# display.net
KiCad netlist of a schematic drawn in EAGLE
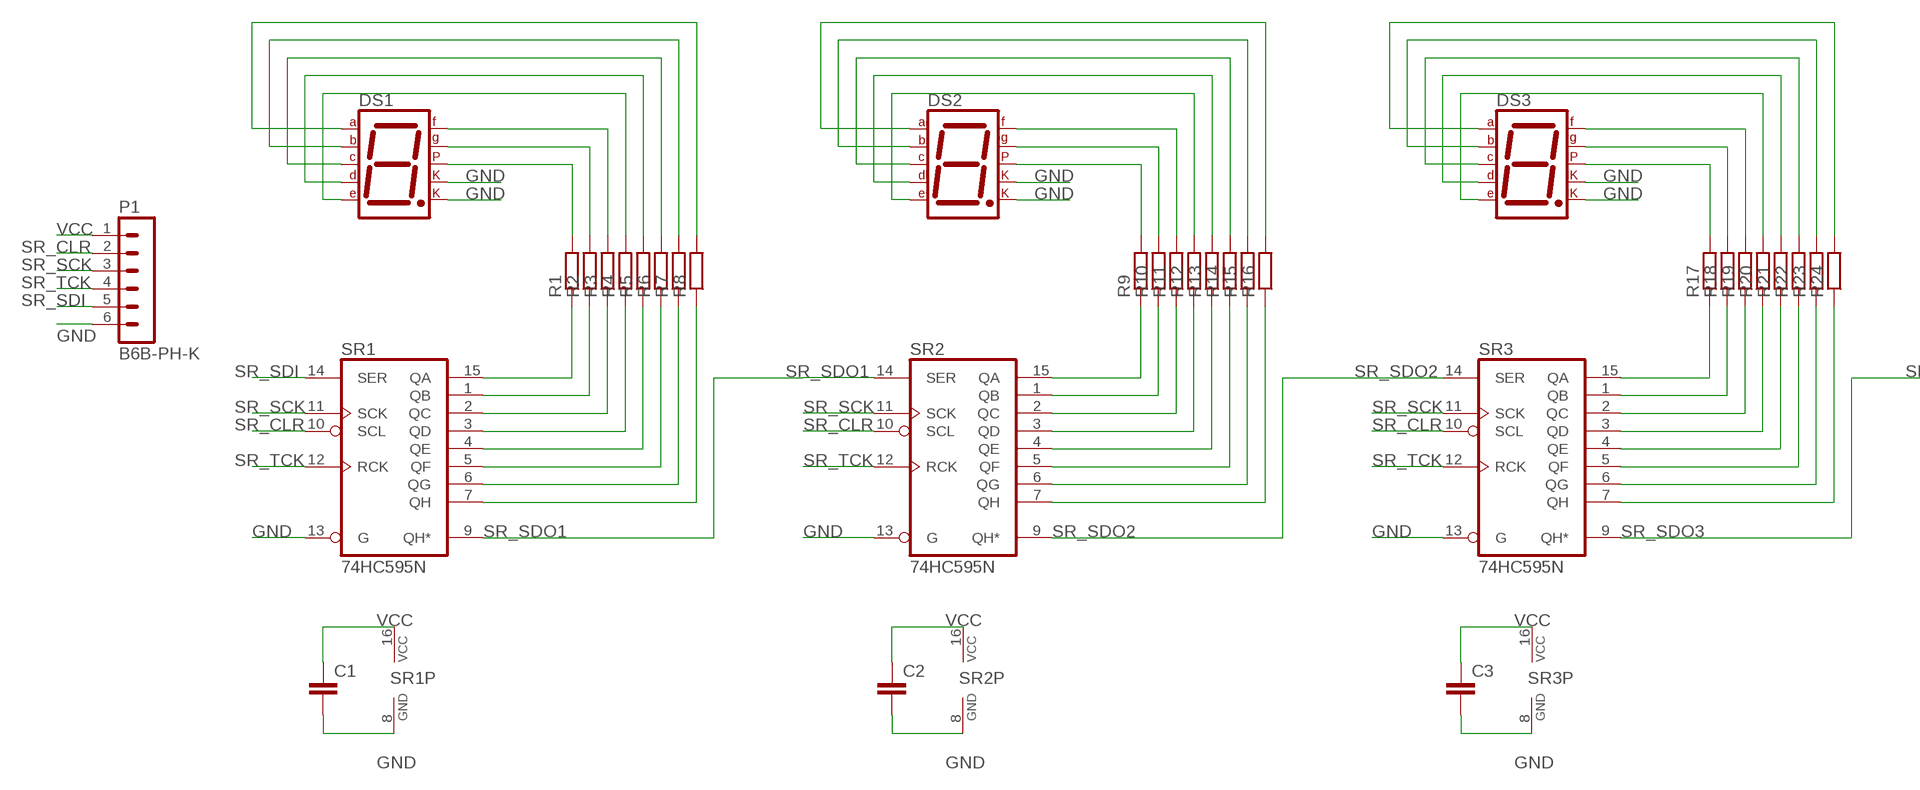
[diagram p0: schematic, sheet 1, part 1 of 2]
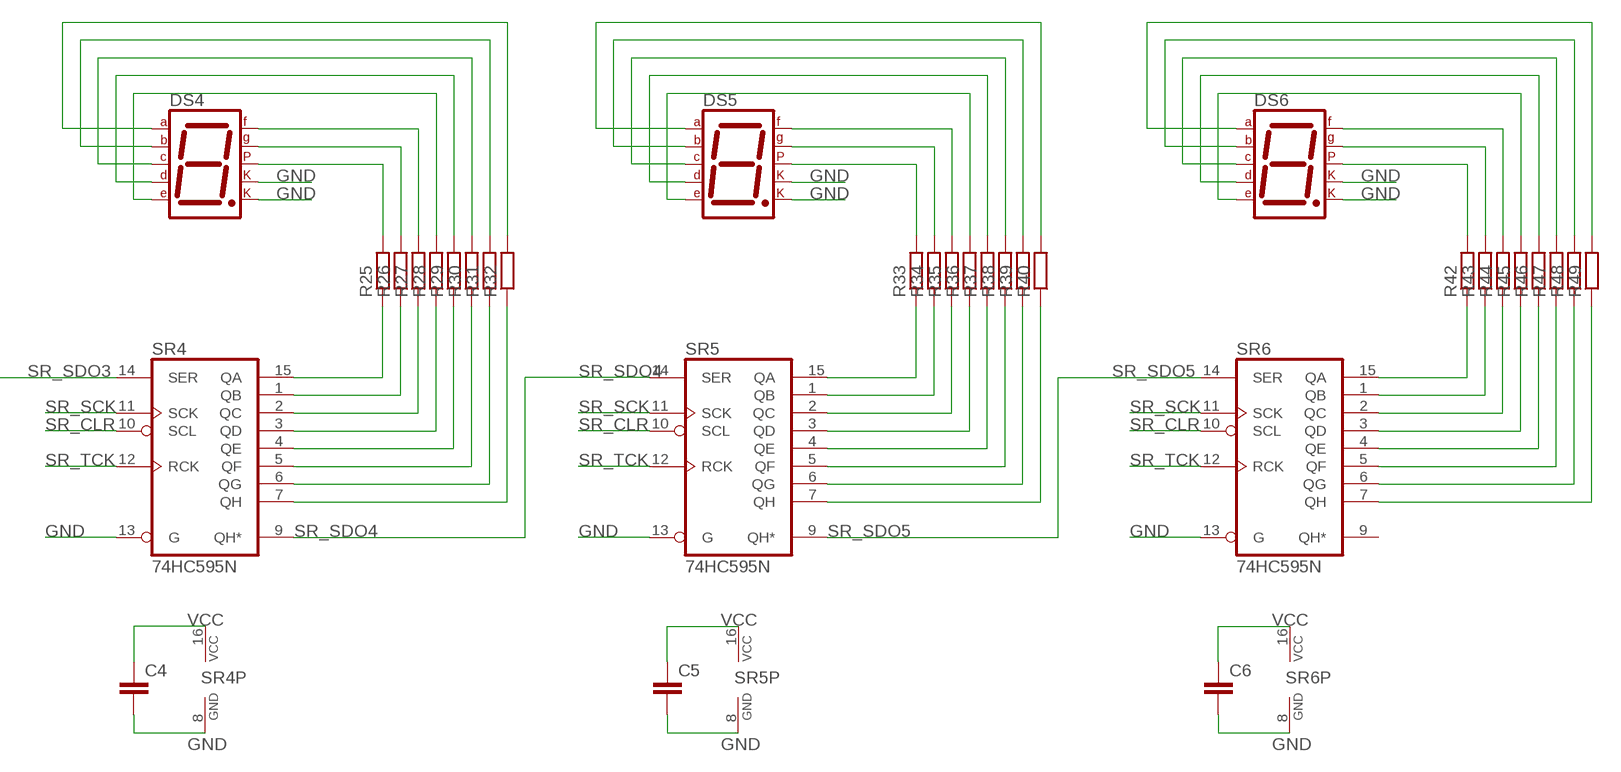
[diagram p1: schematic, sheet 1, part 2 of 2]

(export (version "E")
  (design (tool "Eeschema 10.0.6"))
  (components
    (comp (ref "C1")
      (value "C-EU025-024X044")
      (footprint "eagle-import:C025-024X044")
      (libsource (lib "eagle-import") (part "C-EU025-024X044"))
    )
    (comp (ref "C2")
      (value "C-EU025-024X044")
      (footprint "eagle-import:C025-024X044")
      (libsource (lib "eagle-import") (part "C-EU025-024X044"))
    )
    (comp (ref "C3")
      (value "C-EU025-024X044")
      (footprint "eagle-import:C025-024X044")
      (libsource (lib "eagle-import") (part "C-EU025-024X044"))
    )
    (comp (ref "C4")
      (value "C-EU025-024X044")
      (footprint "eagle-import:C025-024X044")
      (libsource (lib "eagle-import") (part "C-EU025-024X044"))
    )
    (comp (ref "C5")
      (value "C-EU025-024X044")
      (footprint "eagle-import:C025-024X044")
      (libsource (lib "eagle-import") (part "C-EU025-024X044"))
    )
    (comp (ref "C6")
      (value "C-EU025-024X044")
      (footprint "eagle-import:C025-024X044")
      (libsource (lib "eagle-import") (part "C-EU025-024X044"))
    )
    (comp (ref "DS1")
      (value "7SEG-CK")
      (footprint "eagle-import:7SEG-13")
      (libsource (lib "eagle-import") (part "7SEG-CK"))
    )
    (comp (ref "DS2")
      (value "7SEG-CK")
      (footprint "eagle-import:7SEG-13")
      (libsource (lib "eagle-import") (part "7SEG-CK"))
    )
    (comp (ref "DS3")
      (value "7SEG-CK")
      (footprint "eagle-import:7SEG-13")
      (libsource (lib "eagle-import") (part "7SEG-CK"))
    )
    (comp (ref "DS4")
      (value "7SEG-CK")
      (footprint "eagle-import:7SEG-13")
      (libsource (lib "eagle-import") (part "7SEG-CK"))
    )
    (comp (ref "DS5")
      (value "7SEG-CK")
      (footprint "eagle-import:7SEG-13")
      (libsource (lib "eagle-import") (part "7SEG-CK"))
    )
    (comp (ref "DS6")
      (value "7SEG-CK")
      (footprint "eagle-import:7SEG-13")
      (libsource (lib "eagle-import") (part "7SEG-CK"))
    )
    (comp (ref "P1")
      (value "B6B-PH-K")
      (footprint "eagle-import:B6B-PH-K")
      (libsource (lib "eagle-import") (part "B6B-PH-K"))
    )
    (comp (ref "R1")
      (value "R-EU_0207/10")
      (footprint "eagle-import:0207_10")
      (libsource (lib "eagle-import") (part "R-EU_0207/10"))
    )
    (comp (ref "R2")
      (value "R-EU_0207/10")
      (footprint "eagle-import:0207_10")
      (libsource (lib "eagle-import") (part "R-EU_0207/10"))
    )
    (comp (ref "R3")
      (value "R-EU_0207/10")
      (footprint "eagle-import:0207_10")
      (libsource (lib "eagle-import") (part "R-EU_0207/10"))
    )
    (comp (ref "R4")
      (value "R-EU_0207/10")
      (footprint "eagle-import:0207_10")
      (libsource (lib "eagle-import") (part "R-EU_0207/10"))
    )
    (comp (ref "R5")
      (value "R-EU_0207/10")
      (footprint "eagle-import:0207_10")
      (libsource (lib "eagle-import") (part "R-EU_0207/10"))
    )
    (comp (ref "R6")
      (value "R-EU_0207/10")
      (footprint "eagle-import:0207_10")
      (libsource (lib "eagle-import") (part "R-EU_0207/10"))
    )
    (comp (ref "R7")
      (value "R-EU_0207/10")
      (footprint "eagle-import:0207_10")
      (libsource (lib "eagle-import") (part "R-EU_0207/10"))
    )
    (comp (ref "R8")
      (value "R-EU_0207/10")
      (footprint "eagle-import:0207_10")
      (libsource (lib "eagle-import") (part "R-EU_0207/10"))
    )
    (comp (ref "R9")
      (value "R-EU_0207/10")
      (footprint "eagle-import:0207_10")
      (libsource (lib "eagle-import") (part "R-EU_0207/10"))
    )
    (comp (ref "R10")
      (value "R-EU_0207/10")
      (footprint "eagle-import:0207_10")
      (libsource (lib "eagle-import") (part "R-EU_0207/10"))
    )
    (comp (ref "R11")
      (value "R-EU_0207/10")
      (footprint "eagle-import:0207_10")
      (libsource (lib "eagle-import") (part "R-EU_0207/10"))
    )
    (comp (ref "R12")
      (value "R-EU_0207/10")
      (footprint "eagle-import:0207_10")
      (libsource (lib "eagle-import") (part "R-EU_0207/10"))
    )
    (comp (ref "R13")
      (value "R-EU_0207/10")
      (footprint "eagle-import:0207_10")
      (libsource (lib "eagle-import") (part "R-EU_0207/10"))
    )
    (comp (ref "R14")
      (value "R-EU_0207/10")
      (footprint "eagle-import:0207_10")
      (libsource (lib "eagle-import") (part "R-EU_0207/10"))
    )
    (comp (ref "R15")
      (value "R-EU_0207/10")
      (footprint "eagle-import:0207_10")
      (libsource (lib "eagle-import") (part "R-EU_0207/10"))
    )
    (comp (ref "R16")
      (value "R-EU_0207/10")
      (footprint "eagle-import:0207_10")
      (libsource (lib "eagle-import") (part "R-EU_0207/10"))
    )
    (comp (ref "R17")
      (value "R-EU_0207/10")
      (footprint "eagle-import:0207_10")
      (libsource (lib "eagle-import") (part "R-EU_0207/10"))
    )
    (comp (ref "R18")
      (value "R-EU_0207/10")
      (footprint "eagle-import:0207_10")
      (libsource (lib "eagle-import") (part "R-EU_0207/10"))
    )
    (comp (ref "R19")
      (value "R-EU_0207/10")
      (footprint "eagle-import:0207_10")
      (libsource (lib "eagle-import") (part "R-EU_0207/10"))
    )
    (comp (ref "R20")
      (value "R-EU_0207/10")
      (footprint "eagle-import:0207_10")
      (libsource (lib "eagle-import") (part "R-EU_0207/10"))
    )
    (comp (ref "R21")
      (value "R-EU_0207/10")
      (footprint "eagle-import:0207_10")
      (libsource (lib "eagle-import") (part "R-EU_0207/10"))
    )
    (comp (ref "R22")
      (value "R-EU_0207/10")
      (footprint "eagle-import:0207_10")
      (libsource (lib "eagle-import") (part "R-EU_0207/10"))
    )
    (comp (ref "R23")
      (value "R-EU_0207/10")
      (footprint "eagle-import:0207_10")
      (libsource (lib "eagle-import") (part "R-EU_0207/10"))
    )
    (comp (ref "R24")
      (value "R-EU_0207/10")
      (footprint "eagle-import:0207_10")
      (libsource (lib "eagle-import") (part "R-EU_0207/10"))
    )
    (comp (ref "R25")
      (value "R-EU_0207/10")
      (footprint "eagle-import:0207_10")
      (libsource (lib "eagle-import") (part "R-EU_0207/10"))
    )
    (comp (ref "R26")
      (value "R-EU_0207/10")
      (footprint "eagle-import:0207_10")
      (libsource (lib "eagle-import") (part "R-EU_0207/10"))
    )
    (comp (ref "R27")
      (value "R-EU_0207/10")
      (footprint "eagle-import:0207_10")
      (libsource (lib "eagle-import") (part "R-EU_0207/10"))
    )
    (comp (ref "R28")
      (value "R-EU_0207/10")
      (footprint "eagle-import:0207_10")
      (libsource (lib "eagle-import") (part "R-EU_0207/10"))
    )
    (comp (ref "R29")
      (value "R-EU_0207/10")
      (footprint "eagle-import:0207_10")
      (libsource (lib "eagle-import") (part "R-EU_0207/10"))
    )
    (comp (ref "R30")
      (value "R-EU_0207/10")
      (footprint "eagle-import:0207_10")
      (libsource (lib "eagle-import") (part "R-EU_0207/10"))
    )
    (comp (ref "R31")
      (value "R-EU_0207/10")
      (footprint "eagle-import:0207_10")
      (libsource (lib "eagle-import") (part "R-EU_0207/10"))
    )
    (comp (ref "R32")
      (value "R-EU_0207/10")
      (footprint "eagle-import:0207_10")
      (libsource (lib "eagle-import") (part "R-EU_0207/10"))
    )
    (comp (ref "R33")
      (value "R-EU_0207/10")
      (footprint "eagle-import:0207_10")
      (libsource (lib "eagle-import") (part "R-EU_0207/10"))
    )
    (comp (ref "R34")
      (value "R-EU_0207/10")
      (footprint "eagle-import:0207_10")
      (libsource (lib "eagle-import") (part "R-EU_0207/10"))
    )
    (comp (ref "R35")
      (value "R-EU_0207/10")
      (footprint "eagle-import:0207_10")
      (libsource (lib "eagle-import") (part "R-EU_0207/10"))
    )
    (comp (ref "R36")
      (value "R-EU_0207/10")
      (footprint "eagle-import:0207_10")
      (libsource (lib "eagle-import") (part "R-EU_0207/10"))
    )
    (comp (ref "R37")
      (value "R-EU_0207/10")
      (footprint "eagle-import:0207_10")
      (libsource (lib "eagle-import") (part "R-EU_0207/10"))
    )
    (comp (ref "R38")
      (value "R-EU_0207/10")
      (footprint "eagle-import:0207_10")
      (libsource (lib "eagle-import") (part "R-EU_0207/10"))
    )
    (comp (ref "R39")
      (value "R-EU_0207/10")
      (footprint "eagle-import:0207_10")
      (libsource (lib "eagle-import") (part "R-EU_0207/10"))
    )
    (comp (ref "R40")
      (value "R-EU_0207/10")
      (footprint "eagle-import:0207_10")
      (libsource (lib "eagle-import") (part "R-EU_0207/10"))
    )
    (comp (ref "R42")
      (value "R-EU_0207/10")
      (footprint "eagle-import:0207_10")
      (libsource (lib "eagle-import") (part "R-EU_0207/10"))
    )
    (comp (ref "R43")
      (value "R-EU_0207/10")
      (footprint "eagle-import:0207_10")
      (libsource (lib "eagle-import") (part "R-EU_0207/10"))
    )
    (comp (ref "R44")
      (value "R-EU_0207/10")
      (footprint "eagle-import:0207_10")
      (libsource (lib "eagle-import") (part "R-EU_0207/10"))
    )
    (comp (ref "R45")
      (value "R-EU_0207/10")
      (footprint "eagle-import:0207_10")
      (libsource (lib "eagle-import") (part "R-EU_0207/10"))
    )
    (comp (ref "R46")
      (value "R-EU_0207/10")
      (footprint "eagle-import:0207_10")
      (libsource (lib "eagle-import") (part "R-EU_0207/10"))
    )
    (comp (ref "R47")
      (value "R-EU_0207/10")
      (footprint "eagle-import:0207_10")
      (libsource (lib "eagle-import") (part "R-EU_0207/10"))
    )
    (comp (ref "R48")
      (value "R-EU_0207/10")
      (footprint "eagle-import:0207_10")
      (libsource (lib "eagle-import") (part "R-EU_0207/10"))
    )
    (comp (ref "R49")
      (value "R-EU_0207/10")
      (footprint "eagle-import:0207_10")
      (libsource (lib "eagle-import") (part "R-EU_0207/10"))
    )
    (comp (ref "SR1")
      (value "74HC595N")
      (footprint "eagle-import:DIL16")
      (libsource (lib "eagle-import") (part "74595NHC"))
    )
    (comp (ref "SR2")
      (value "74HC595N")
      (footprint "eagle-import:DIL16")
      (libsource (lib "eagle-import") (part "74595NHC"))
    )
    (comp (ref "SR3")
      (value "74HC595N")
      (footprint "eagle-import:DIL16")
      (libsource (lib "eagle-import") (part "74595NHC"))
    )
    (comp (ref "SR4")
      (value "74HC595N")
      (footprint "eagle-import:DIL16")
      (libsource (lib "eagle-import") (part "74595NHC"))
    )
    (comp (ref "SR5")
      (value "74HC595N")
      (footprint "eagle-import:DIL16")
      (libsource (lib "eagle-import") (part "74595NHC"))
    )
    (comp (ref "SR6")
      (value "74HC595N")
      (footprint "eagle-import:DIL16")
      (libsource (lib "eagle-import") (part "74595NHC"))
    )
  )
  (nets
    (net (code "1") (name "/GND") (class "Default")
      (node (ref "C1") (pin "2") (pinfunction "2_2") (pintype "passive"))
      (node (ref "C2") (pin "2") (pinfunction "2_2") (pintype "passive"))
      (node (ref "C3") (pin "2") (pinfunction "2_2") (pintype "passive"))
      (node (ref "C4") (pin "2") (pinfunction "2_2") (pintype "passive"))
      (node (ref "C5") (pin "2") (pinfunction "2_2") (pintype "passive"))
      (node (ref "C6") (pin "2") (pinfunction "2_2") (pintype "passive"))
      (node (ref "DS1") (pin "3") (pinfunction "CK1_3") (pintype "passive"))
      (node (ref "DS1") (pin "8") (pinfunction "CK2_8") (pintype "passive"))
      (node (ref "DS2") (pin "3") (pinfunction "CK1_3") (pintype "passive"))
      (node (ref "DS2") (pin "8") (pinfunction "CK2_8") (pintype "passive"))
      (node (ref "DS3") (pin "3") (pinfunction "CK1_3") (pintype "passive"))
      (node (ref "DS3") (pin "8") (pinfunction "CK2_8") (pintype "passive"))
      (node (ref "DS4") (pin "3") (pinfunction "CK1_3") (pintype "passive"))
      (node (ref "DS4") (pin "8") (pinfunction "CK2_8") (pintype "passive"))
      (node (ref "DS5") (pin "3") (pinfunction "CK1_3") (pintype "passive"))
      (node (ref "DS5") (pin "8") (pinfunction "CK2_8") (pintype "passive"))
      (node (ref "DS6") (pin "3") (pinfunction "CK1_3") (pintype "passive"))
      (node (ref "DS6") (pin "8") (pinfunction "CK2_8") (pintype "passive"))
      (node (ref "P1") (pin "6") (pinfunction "6_6") (pintype "passive"))
      (node (ref "SR1") (pin "13") (pinfunction "G_13") (pintype "input"))
      (node (ref "SR1") (pin "8") (pinfunction "GND_8") (pintype "power_in"))
      (node (ref "SR2") (pin "13") (pinfunction "G_13") (pintype "input"))
      (node (ref "SR2") (pin "8") (pinfunction "GND_8") (pintype "power_in"))
      (node (ref "SR3") (pin "13") (pinfunction "G_13") (pintype "input"))
      (node (ref "SR3") (pin "8") (pinfunction "GND_8") (pintype "power_in"))
      (node (ref "SR4") (pin "13") (pinfunction "G_13") (pintype "input"))
      (node (ref "SR4") (pin "8") (pinfunction "GND_8") (pintype "power_in"))
      (node (ref "SR5") (pin "13") (pinfunction "G_13") (pintype "input"))
      (node (ref "SR5") (pin "8") (pinfunction "GND_8") (pintype "power_in"))
      (node (ref "SR6") (pin "13") (pinfunction "G_13") (pintype "input"))
      (node (ref "SR6") (pin "8") (pinfunction "GND_8") (pintype "power_in"))
    )
    (net (code "2") (name "/SR_CLR") (class "Default")
      (node (ref "P1") (pin "2") (pinfunction "2_2") (pintype "passive"))
      (node (ref "SR1") (pin "10") (pinfunction "SCL_10") (pintype "input"))
      (node (ref "SR2") (pin "10") (pinfunction "SCL_10") (pintype "input"))
      (node (ref "SR3") (pin "10") (pinfunction "SCL_10") (pintype "input"))
      (node (ref "SR4") (pin "10") (pinfunction "SCL_10") (pintype "input"))
      (node (ref "SR5") (pin "10") (pinfunction "SCL_10") (pintype "input"))
      (node (ref "SR6") (pin "10") (pinfunction "SCL_10") (pintype "input"))
    )
    (net (code "3") (name "/SR_SCK") (class "Default")
      (node (ref "P1") (pin "3") (pinfunction "3_3") (pintype "passive"))
      (node (ref "SR1") (pin "11") (pinfunction "SCK_11") (pintype "input"))
      (node (ref "SR2") (pin "11") (pinfunction "SCK_11") (pintype "input"))
      (node (ref "SR3") (pin "11") (pinfunction "SCK_11") (pintype "input"))
      (node (ref "SR4") (pin "11") (pinfunction "SCK_11") (pintype "input"))
      (node (ref "SR5") (pin "11") (pinfunction "SCK_11") (pintype "input"))
      (node (ref "SR6") (pin "11") (pinfunction "SCK_11") (pintype "input"))
    )
    (net (code "4") (name "/SR_SDI") (class "Default")
      (node (ref "P1") (pin "5") (pinfunction "5_5") (pintype "passive"))
      (node (ref "SR1") (pin "14") (pinfunction "SER_14") (pintype "input"))
    )
    (net (code "5") (name "/SR_SDO1") (class "Default")
      (node (ref "SR1") (pin "9") (pinfunction "QH*_9") (pintype "tri_state"))
      (node (ref "SR2") (pin "14") (pinfunction "SER_14") (pintype "input"))
    )
    (net (code "6") (name "/SR_SDO2") (class "Default")
      (node (ref "SR2") (pin "9") (pinfunction "QH*_9") (pintype "tri_state"))
      (node (ref "SR3") (pin "14") (pinfunction "SER_14") (pintype "input"))
    )
    (net (code "7") (name "/SR_SDO3") (class "Default")
      (node (ref "SR3") (pin "9") (pinfunction "QH*_9") (pintype "tri_state"))
      (node (ref "SR4") (pin "14") (pinfunction "SER_14") (pintype "input"))
    )
    (net (code "8") (name "/SR_SDO4") (class "Default")
      (node (ref "SR4") (pin "9") (pinfunction "QH*_9") (pintype "tri_state"))
      (node (ref "SR5") (pin "14") (pinfunction "SER_14") (pintype "input"))
    )
    (net (code "9") (name "/SR_SDO5") (class "Default")
      (node (ref "SR5") (pin "9") (pinfunction "QH*_9") (pintype "tri_state"))
      (node (ref "SR6") (pin "14") (pinfunction "SER_14") (pintype "input"))
    )
    (net (code "10") (name "/SR_TCK") (class "Default")
      (node (ref "P1") (pin "4") (pinfunction "4_4") (pintype "passive"))
      (node (ref "SR1") (pin "12") (pinfunction "RCK_12") (pintype "input"))
      (node (ref "SR2") (pin "12") (pinfunction "RCK_12") (pintype "input"))
      (node (ref "SR3") (pin "12") (pinfunction "RCK_12") (pintype "input"))
      (node (ref "SR4") (pin "12") (pinfunction "RCK_12") (pintype "input"))
      (node (ref "SR5") (pin "12") (pinfunction "RCK_12") (pintype "input"))
      (node (ref "SR6") (pin "12") (pinfunction "RCK_12") (pintype "input"))
    )
    (net (code "11") (name "/VCC") (class "Default")
      (node (ref "C1") (pin "1") (pinfunction "1_1") (pintype "passive"))
      (node (ref "C2") (pin "1") (pinfunction "1_1") (pintype "passive"))
      (node (ref "C3") (pin "1") (pinfunction "1_1") (pintype "passive"))
      (node (ref "C4") (pin "1") (pinfunction "1_1") (pintype "passive"))
      (node (ref "C5") (pin "1") (pinfunction "1_1") (pintype "passive"))
      (node (ref "C6") (pin "1") (pinfunction "1_1") (pintype "passive"))
      (node (ref "P1") (pin "1") (pinfunction "1_1") (pintype "passive"))
      (node (ref "SR1") (pin "16") (pinfunction "VCC_16") (pintype "power_in"))
      (node (ref "SR2") (pin "16") (pinfunction "VCC_16") (pintype "power_in"))
      (node (ref "SR3") (pin "16") (pinfunction "VCC_16") (pintype "power_in"))
      (node (ref "SR4") (pin "16") (pinfunction "VCC_16") (pintype "power_in"))
      (node (ref "SR5") (pin "16") (pinfunction "VCC_16") (pintype "power_in"))
      (node (ref "SR6") (pin "16") (pinfunction "VCC_16") (pintype "power_in"))
    )
    (net (code "12") (name "Net-(DS1-A)") (class "Default")
      (node (ref "DS1") (pin "7") (pinfunction "A_7") (pintype "passive"))
      (node (ref "R8") (pin "2") (pinfunction "2_2") (pintype "passive"))
    )
    (net (code "13") (name "Net-(DS1-B)") (class "Default")
      (node (ref "DS1") (pin "6") (pinfunction "B_6") (pintype "passive"))
      (node (ref "R7") (pin "2") (pinfunction "2_2") (pintype "passive"))
    )
    (net (code "14") (name "Net-(DS1-C)") (class "Default")
      (node (ref "DS1") (pin "4") (pinfunction "C_4") (pintype "passive"))
      (node (ref "R6") (pin "2") (pinfunction "2_2") (pintype "passive"))
    )
    (net (code "15") (name "Net-(DS1-D)") (class "Default")
      (node (ref "DS1") (pin "2") (pinfunction "D_2") (pintype "passive"))
      (node (ref "R5") (pin "2") (pinfunction "2_2") (pintype "passive"))
    )
    (net (code "16") (name "Net-(DS1-DP)") (class "Default")
      (node (ref "DS1") (pin "5") (pinfunction "DP_5") (pintype "passive"))
      (node (ref "R1") (pin "2") (pinfunction "2_2") (pintype "passive"))
    )
    (net (code "17") (name "Net-(DS1-E)") (class "Default")
      (node (ref "DS1") (pin "1") (pinfunction "E_1") (pintype "passive"))
      (node (ref "R4") (pin "2") (pinfunction "2_2") (pintype "passive"))
    )
    (net (code "18") (name "Net-(DS1-F)") (class "Default")
      (node (ref "DS1") (pin "9") (pinfunction "F_9") (pintype "passive"))
      (node (ref "R3") (pin "2") (pinfunction "2_2") (pintype "passive"))
    )
    (net (code "19") (name "Net-(DS1-G)") (class "Default")
      (node (ref "DS1") (pin "10") (pinfunction "G_10") (pintype "passive"))
      (node (ref "R2") (pin "2") (pinfunction "2_2") (pintype "passive"))
    )
    (net (code "20") (name "Net-(DS2-A)") (class "Default")
      (node (ref "DS2") (pin "7") (pinfunction "A_7") (pintype "passive"))
      (node (ref "R16") (pin "2") (pinfunction "2_2") (pintype "passive"))
    )
    (net (code "21") (name "Net-(DS2-B)") (class "Default")
      (node (ref "DS2") (pin "6") (pinfunction "B_6") (pintype "passive"))
      (node (ref "R15") (pin "2") (pinfunction "2_2") (pintype "passive"))
    )
    (net (code "22") (name "Net-(DS2-C)") (class "Default")
      (node (ref "DS2") (pin "4") (pinfunction "C_4") (pintype "passive"))
      (node (ref "R14") (pin "2") (pinfunction "2_2") (pintype "passive"))
    )
    (net (code "23") (name "Net-(DS2-D)") (class "Default")
      (node (ref "DS2") (pin "2") (pinfunction "D_2") (pintype "passive"))
      (node (ref "R13") (pin "2") (pinfunction "2_2") (pintype "passive"))
    )
    (net (code "24") (name "Net-(DS2-DP)") (class "Default")
      (node (ref "DS2") (pin "5") (pinfunction "DP_5") (pintype "passive"))
      (node (ref "R9") (pin "2") (pinfunction "2_2") (pintype "passive"))
    )
    (net (code "25") (name "Net-(DS2-E)") (class "Default")
      (node (ref "DS2") (pin "1") (pinfunction "E_1") (pintype "passive"))
      (node (ref "R12") (pin "2") (pinfunction "2_2") (pintype "passive"))
    )
    (net (code "26") (name "Net-(DS2-F)") (class "Default")
      (node (ref "DS2") (pin "9") (pinfunction "F_9") (pintype "passive"))
      (node (ref "R11") (pin "2") (pinfunction "2_2") (pintype "passive"))
    )
    (net (code "27") (name "Net-(DS2-G)") (class "Default")
      (node (ref "DS2") (pin "10") (pinfunction "G_10") (pintype "passive"))
      (node (ref "R10") (pin "2") (pinfunction "2_2") (pintype "passive"))
    )
    (net (code "28") (name "Net-(DS3-A)") (class "Default")
      (node (ref "DS3") (pin "7") (pinfunction "A_7") (pintype "passive"))
      (node (ref "R24") (pin "2") (pinfunction "2_2") (pintype "passive"))
    )
    (net (code "29") (name "Net-(DS3-B)") (class "Default")
      (node (ref "DS3") (pin "6") (pinfunction "B_6") (pintype "passive"))
      (node (ref "R23") (pin "2") (pinfunction "2_2") (pintype "passive"))
    )
    (net (code "30") (name "Net-(DS3-C)") (class "Default")
      (node (ref "DS3") (pin "4") (pinfunction "C_4") (pintype "passive"))
      (node (ref "R22") (pin "2") (pinfunction "2_2") (pintype "passive"))
    )
    (net (code "31") (name "Net-(DS3-D)") (class "Default")
      (node (ref "DS3") (pin "2") (pinfunction "D_2") (pintype "passive"))
      (node (ref "R21") (pin "2") (pinfunction "2_2") (pintype "passive"))
    )
    (net (code "32") (name "Net-(DS3-DP)") (class "Default")
      (node (ref "DS3") (pin "5") (pinfunction "DP_5") (pintype "passive"))
      (node (ref "R17") (pin "2") (pinfunction "2_2") (pintype "passive"))
    )
    (net (code "33") (name "Net-(DS3-E)") (class "Default")
      (node (ref "DS3") (pin "1") (pinfunction "E_1") (pintype "passive"))
      (node (ref "R20") (pin "2") (pinfunction "2_2") (pintype "passive"))
    )
    (net (code "34") (name "Net-(DS3-F)") (class "Default")
      (node (ref "DS3") (pin "9") (pinfunction "F_9") (pintype "passive"))
      (node (ref "R19") (pin "2") (pinfunction "2_2") (pintype "passive"))
    )
    (net (code "35") (name "Net-(DS3-G)") (class "Default")
      (node (ref "DS3") (pin "10") (pinfunction "G_10") (pintype "passive"))
      (node (ref "R18") (pin "2") (pinfunction "2_2") (pintype "passive"))
    )
    (net (code "36") (name "Net-(DS4-A)") (class "Default")
      (node (ref "DS4") (pin "7") (pinfunction "A_7") (pintype "passive"))
      (node (ref "R32") (pin "2") (pinfunction "2_2") (pintype "passive"))
    )
    (net (code "37") (name "Net-(DS4-B)") (class "Default")
      (node (ref "DS4") (pin "6") (pinfunction "B_6") (pintype "passive"))
      (node (ref "R31") (pin "2") (pinfunction "2_2") (pintype "passive"))
    )
    (net (code "38") (name "Net-(DS4-C)") (class "Default")
      (node (ref "DS4") (pin "4") (pinfunction "C_4") (pintype "passive"))
      (node (ref "R30") (pin "2") (pinfunction "2_2") (pintype "passive"))
    )
    (net (code "39") (name "Net-(DS4-D)") (class "Default")
      (node (ref "DS4") (pin "2") (pinfunction "D_2") (pintype "passive"))
      (node (ref "R29") (pin "2") (pinfunction "2_2") (pintype "passive"))
    )
    (net (code "40") (name "Net-(DS4-DP)") (class "Default")
      (node (ref "DS4") (pin "5") (pinfunction "DP_5") (pintype "passive"))
      (node (ref "R25") (pin "2") (pinfunction "2_2") (pintype "passive"))
    )
    (net (code "41") (name "Net-(DS4-E)") (class "Default")
      (node (ref "DS4") (pin "1") (pinfunction "E_1") (pintype "passive"))
      (node (ref "R28") (pin "2") (pinfunction "2_2") (pintype "passive"))
    )
    (net (code "42") (name "Net-(DS4-F)") (class "Default")
      (node (ref "DS4") (pin "9") (pinfunction "F_9") (pintype "passive"))
      (node (ref "R27") (pin "2") (pinfunction "2_2") (pintype "passive"))
    )
    (net (code "43") (name "Net-(DS4-G)") (class "Default")
      (node (ref "DS4") (pin "10") (pinfunction "G_10") (pintype "passive"))
      (node (ref "R26") (pin "2") (pinfunction "2_2") (pintype "passive"))
    )
    (net (code "44") (name "Net-(DS5-A)") (class "Default")
      (node (ref "DS5") (pin "7") (pinfunction "A_7") (pintype "passive"))
      (node (ref "R40") (pin "2") (pinfunction "2_2") (pintype "passive"))
    )
    (net (code "45") (name "Net-(DS5-B)") (class "Default")
      (node (ref "DS5") (pin "6") (pinfunction "B_6") (pintype "passive"))
      (node (ref "R39") (pin "2") (pinfunction "2_2") (pintype "passive"))
    )
    (net (code "46") (name "Net-(DS5-C)") (class "Default")
      (node (ref "DS5") (pin "4") (pinfunction "C_4") (pintype "passive"))
      (node (ref "R38") (pin "2") (pinfunction "2_2") (pintype "passive"))
    )
    (net (code "47") (name "Net-(DS5-D)") (class "Default")
      (node (ref "DS5") (pin "2") (pinfunction "D_2") (pintype "passive"))
      (node (ref "R37") (pin "2") (pinfunction "2_2") (pintype "passive"))
    )
    (net (code "48") (name "Net-(DS5-DP)") (class "Default")
      (node (ref "DS5") (pin "5") (pinfunction "DP_5") (pintype "passive"))
      (node (ref "R33") (pin "2") (pinfunction "2_2") (pintype "passive"))
    )
    (net (code "49") (name "Net-(DS5-E)") (class "Default")
      (node (ref "DS5") (pin "1") (pinfunction "E_1") (pintype "passive"))
      (node (ref "R36") (pin "2") (pinfunction "2_2") (pintype "passive"))
    )
    (net (code "50") (name "Net-(DS5-F)") (class "Default")
      (node (ref "DS5") (pin "9") (pinfunction "F_9") (pintype "passive"))
      (node (ref "R35") (pin "2") (pinfunction "2_2") (pintype "passive"))
    )
    (net (code "51") (name "Net-(DS5-G)") (class "Default")
      (node (ref "DS5") (pin "10") (pinfunction "G_10") (pintype "passive"))
      (node (ref "R34") (pin "2") (pinfunction "2_2") (pintype "passive"))
    )
    (net (code "52") (name "Net-(DS6-A)") (class "Default")
      (node (ref "DS6") (pin "7") (pinfunction "A_7") (pintype "passive"))
      (node (ref "R49") (pin "2") (pinfunction "2_2") (pintype "passive"))
    )
    (net (code "53") (name "Net-(DS6-B)") (class "Default")
      (node (ref "DS6") (pin "6") (pinfunction "B_6") (pintype "passive"))
      (node (ref "R48") (pin "2") (pinfunction "2_2") (pintype "passive"))
    )
    (net (code "54") (name "Net-(DS6-C)") (class "Default")
      (node (ref "DS6") (pin "4") (pinfunction "C_4") (pintype "passive"))
      (node (ref "R47") (pin "2") (pinfunction "2_2") (pintype "passive"))
    )
    (net (code "55") (name "Net-(DS6-D)") (class "Default")
      (node (ref "DS6") (pin "2") (pinfunction "D_2") (pintype "passive"))
      (node (ref "R46") (pin "2") (pinfunction "2_2") (pintype "passive"))
    )
    (net (code "56") (name "Net-(DS6-DP)") (class "Default")
      (node (ref "DS6") (pin "5") (pinfunction "DP_5") (pintype "passive"))
      (node (ref "R42") (pin "2") (pinfunction "2_2") (pintype "passive"))
    )
    (net (code "57") (name "Net-(DS6-E)") (class "Default")
      (node (ref "DS6") (pin "1") (pinfunction "E_1") (pintype "passive"))
      (node (ref "R45") (pin "2") (pinfunction "2_2") (pintype "passive"))
    )
    (net (code "58") (name "Net-(DS6-F)") (class "Default")
      (node (ref "DS6") (pin "9") (pinfunction "F_9") (pintype "passive"))
      (node (ref "R44") (pin "2") (pinfunction "2_2") (pintype "passive"))
    )
    (net (code "59") (name "Net-(DS6-G)") (class "Default")
      (node (ref "DS6") (pin "10") (pinfunction "G_10") (pintype "passive"))
      (node (ref "R43") (pin "2") (pinfunction "2_2") (pintype "passive"))
    )
    (net (code "60") (name "Net-(SR1A-QA)") (class "Default")
      (node (ref "R1") (pin "1") (pinfunction "1_1") (pintype "passive"))
      (node (ref "SR1") (pin "15") (pinfunction "QA_15") (pintype "tri_state"))
    )
    (net (code "61") (name "Net-(SR1A-QB)") (class "Default")
      (node (ref "R2") (pin "1") (pinfunction "1_1") (pintype "passive"))
      (node (ref "SR1") (pin "1") (pinfunction "QB_1") (pintype "tri_state"))
    )
    (net (code "62") (name "Net-(SR1A-QC)") (class "Default")
      (node (ref "R3") (pin "1") (pinfunction "1_1") (pintype "passive"))
      (node (ref "SR1") (pin "2") (pinfunction "QC_2") (pintype "tri_state"))
    )
    (net (code "63") (name "Net-(SR1A-QD)") (class "Default")
      (node (ref "R4") (pin "1") (pinfunction "1_1") (pintype "passive"))
      (node (ref "SR1") (pin "3") (pinfunction "QD_3") (pintype "tri_state"))
    )
    (net (code "64") (name "Net-(SR1A-QE)") (class "Default")
      (node (ref "R5") (pin "1") (pinfunction "1_1") (pintype "passive"))
      (node (ref "SR1") (pin "4") (pinfunction "QE_4") (pintype "tri_state"))
    )
    (net (code "65") (name "Net-(SR1A-QF)") (class "Default")
      (node (ref "R6") (pin "1") (pinfunction "1_1") (pintype "passive"))
      (node (ref "SR1") (pin "5") (pinfunction "QF_5") (pintype "tri_state"))
    )
    (net (code "66") (name "Net-(SR1A-QG)") (class "Default")
      (node (ref "R7") (pin "1") (pinfunction "1_1") (pintype "passive"))
      (node (ref "SR1") (pin "6") (pinfunction "QG_6") (pintype "tri_state"))
    )
    (net (code "67") (name "Net-(SR1A-QH)") (class "Default")
      (node (ref "R8") (pin "1") (pinfunction "1_1") (pintype "passive"))
      (node (ref "SR1") (pin "7") (pinfunction "QH_7") (pintype "tri_state"))
    )
    (net (code "68") (name "Net-(SR2A-QA)") (class "Default")
      (node (ref "R9") (pin "1") (pinfunction "1_1") (pintype "passive"))
      (node (ref "SR2") (pin "15") (pinfunction "QA_15") (pintype "tri_state"))
    )
    (net (code "69") (name "Net-(SR2A-QB)") (class "Default")
      (node (ref "R10") (pin "1") (pinfunction "1_1") (pintype "passive"))
      (node (ref "SR2") (pin "1") (pinfunction "QB_1") (pintype "tri_state"))
    )
    (net (code "70") (name "Net-(SR2A-QC)") (class "Default")
      (node (ref "R11") (pin "1") (pinfunction "1_1") (pintype "passive"))
      (node (ref "SR2") (pin "2") (pinfunction "QC_2") (pintype "tri_state"))
    )
    (net (code "71") (name "Net-(SR2A-QD)") (class "Default")
      (node (ref "R12") (pin "1") (pinfunction "1_1") (pintype "passive"))
      (node (ref "SR2") (pin "3") (pinfunction "QD_3") (pintype "tri_state"))
    )
    (net (code "72") (name "Net-(SR2A-QE)") (class "Default")
      (node (ref "R13") (pin "1") (pinfunction "1_1") (pintype "passive"))
      (node (ref "SR2") (pin "4") (pinfunction "QE_4") (pintype "tri_state"))
    )
    (net (code "73") (name "Net-(SR2A-QF)") (class "Default")
      (node (ref "R14") (pin "1") (pinfunction "1_1") (pintype "passive"))
      (node (ref "SR2") (pin "5") (pinfunction "QF_5") (pintype "tri_state"))
    )
    (net (code "74") (name "Net-(SR2A-QG)") (class "Default")
      (node (ref "R15") (pin "1") (pinfunction "1_1") (pintype "passive"))
      (node (ref "SR2") (pin "6") (pinfunction "QG_6") (pintype "tri_state"))
    )
    (net (code "75") (name "Net-(SR2A-QH)") (class "Default")
      (node (ref "R16") (pin "1") (pinfunction "1_1") (pintype "passive"))
      (node (ref "SR2") (pin "7") (pinfunction "QH_7") (pintype "tri_state"))
    )
    (net (code "76") (name "Net-(SR3A-QA)") (class "Default")
      (node (ref "R17") (pin "1") (pinfunction "1_1") (pintype "passive"))
      (node (ref "SR3") (pin "15") (pinfunction "QA_15") (pintype "tri_state"))
    )
    (net (code "77") (name "Net-(SR3A-QB)") (class "Default")
      (node (ref "R18") (pin "1") (pinfunction "1_1") (pintype "passive"))
      (node (ref "SR3") (pin "1") (pinfunction "QB_1") (pintype "tri_state"))
    )
    (net (code "78") (name "Net-(SR3A-QC)") (class "Default")
      (node (ref "R19") (pin "1") (pinfunction "1_1") (pintype "passive"))
      (node (ref "SR3") (pin "2") (pinfunction "QC_2") (pintype "tri_state"))
    )
    (net (code "79") (name "Net-(SR3A-QD)") (class "Default")
      (node (ref "R20") (pin "1") (pinfunction "1_1") (pintype "passive"))
      (node (ref "SR3") (pin "3") (pinfunction "QD_3") (pintype "tri_state"))
    )
    (net (code "80") (name "Net-(SR3A-QE)") (class "Default")
      (node (ref "R21") (pin "1") (pinfunction "1_1") (pintype "passive"))
      (node (ref "SR3") (pin "4") (pinfunction "QE_4") (pintype "tri_state"))
    )
    (net (code "81") (name "Net-(SR3A-QF)") (class "Default")
      (node (ref "R22") (pin "1") (pinfunction "1_1") (pintype "passive"))
      (node (ref "SR3") (pin "5") (pinfunction "QF_5") (pintype "tri_state"))
    )
    (net (code "82") (name "Net-(SR3A-QG)") (class "Default")
      (node (ref "R23") (pin "1") (pinfunction "1_1") (pintype "passive"))
      (node (ref "SR3") (pin "6") (pinfunction "QG_6") (pintype "tri_state"))
    )
    (net (code "83") (name "Net-(SR3A-QH)") (class "Default")
      (node (ref "R24") (pin "1") (pinfunction "1_1") (pintype "passive"))
      (node (ref "SR3") (pin "7") (pinfunction "QH_7") (pintype "tri_state"))
    )
    (net (code "84") (name "Net-(SR4A-QA)") (class "Default")
      (node (ref "R25") (pin "1") (pinfunction "1_1") (pintype "passive"))
      (node (ref "SR4") (pin "15") (pinfunction "QA_15") (pintype "tri_state"))
    )
    (net (code "85") (name "Net-(SR4A-QB)") (class "Default")
      (node (ref "R26") (pin "1") (pinfunction "1_1") (pintype "passive"))
      (node (ref "SR4") (pin "1") (pinfunction "QB_1") (pintype "tri_state"))
    )
    (net (code "86") (name "Net-(SR4A-QC)") (class "Default")
      (node (ref "R27") (pin "1") (pinfunction "1_1") (pintype "passive"))
      (node (ref "SR4") (pin "2") (pinfunction "QC_2") (pintype "tri_state"))
    )
    (net (code "87") (name "Net-(SR4A-QD)") (class "Default")
      (node (ref "R28") (pin "1") (pinfunction "1_1") (pintype "passive"))
      (node (ref "SR4") (pin "3") (pinfunction "QD_3") (pintype "tri_state"))
    )
    (net (code "88") (name "Net-(SR4A-QE)") (class "Default")
      (node (ref "R29") (pin "1") (pinfunction "1_1") (pintype "passive"))
      (node (ref "SR4") (pin "4") (pinfunction "QE_4") (pintype "tri_state"))
    )
    (net (code "89") (name "Net-(SR4A-QF)") (class "Default")
      (node (ref "R30") (pin "1") (pinfunction "1_1") (pintype "passive"))
      (node (ref "SR4") (pin "5") (pinfunction "QF_5") (pintype "tri_state"))
    )
    (net (code "90") (name "Net-(SR4A-QG)") (class "Default")
      (node (ref "R31") (pin "1") (pinfunction "1_1") (pintype "passive"))
      (node (ref "SR4") (pin "6") (pinfunction "QG_6") (pintype "tri_state"))
    )
    (net (code "91") (name "Net-(SR4A-QH)") (class "Default")
      (node (ref "R32") (pin "1") (pinfunction "1_1") (pintype "passive"))
      (node (ref "SR4") (pin "7") (pinfunction "QH_7") (pintype "tri_state"))
    )
    (net (code "92") (name "Net-(SR5A-QA)") (class "Default")
      (node (ref "R33") (pin "1") (pinfunction "1_1") (pintype "passive"))
      (node (ref "SR5") (pin "15") (pinfunction "QA_15") (pintype "tri_state"))
    )
    (net (code "93") (name "Net-(SR5A-QB)") (class "Default")
      (node (ref "R34") (pin "1") (pinfunction "1_1") (pintype "passive"))
      (node (ref "SR5") (pin "1") (pinfunction "QB_1") (pintype "tri_state"))
    )
    (net (code "94") (name "Net-(SR5A-QC)") (class "Default")
      (node (ref "R35") (pin "1") (pinfunction "1_1") (pintype "passive"))
      (node (ref "SR5") (pin "2") (pinfunction "QC_2") (pintype "tri_state"))
    )
    (net (code "95") (name "Net-(SR5A-QD)") (class "Default")
      (node (ref "R36") (pin "1") (pinfunction "1_1") (pintype "passive"))
      (node (ref "SR5") (pin "3") (pinfunction "QD_3") (pintype "tri_state"))
    )
    (net (code "96") (name "Net-(SR5A-QE)") (class "Default")
      (node (ref "R37") (pin "1") (pinfunction "1_1") (pintype "passive"))
      (node (ref "SR5") (pin "4") (pinfunction "QE_4") (pintype "tri_state"))
    )
    (net (code "97") (name "Net-(SR5A-QF)") (class "Default")
      (node (ref "R38") (pin "1") (pinfunction "1_1") (pintype "passive"))
      (node (ref "SR5") (pin "5") (pinfunction "QF_5") (pintype "tri_state"))
    )
    (net (code "98") (name "Net-(SR5A-QG)") (class "Default")
      (node (ref "R39") (pin "1") (pinfunction "1_1") (pintype "passive"))
      (node (ref "SR5") (pin "6") (pinfunction "QG_6") (pintype "tri_state"))
    )
    (net (code "99") (name "Net-(SR5A-QH)") (class "Default")
      (node (ref "R40") (pin "1") (pinfunction "1_1") (pintype "passive"))
      (node (ref "SR5") (pin "7") (pinfunction "QH_7") (pintype "tri_state"))
    )
    (net (code "100") (name "Net-(SR6A-QA)") (class "Default")
      (node (ref "R42") (pin "1") (pinfunction "1_1") (pintype "passive"))
      (node (ref "SR6") (pin "15") (pinfunction "QA_15") (pintype "tri_state"))
    )
    (net (code "101") (name "Net-(SR6A-QB)") (class "Default")
      (node (ref "R43") (pin "1") (pinfunction "1_1") (pintype "passive"))
      (node (ref "SR6") (pin "1") (pinfunction "QB_1") (pintype "tri_state"))
    )
    (net (code "102") (name "Net-(SR6A-QC)") (class "Default")
      (node (ref "R44") (pin "1") (pinfunction "1_1") (pintype "passive"))
      (node (ref "SR6") (pin "2") (pinfunction "QC_2") (pintype "tri_state"))
    )
    (net (code "103") (name "Net-(SR6A-QD)") (class "Default")
      (node (ref "R45") (pin "1") (pinfunction "1_1") (pintype "passive"))
      (node (ref "SR6") (pin "3") (pinfunction "QD_3") (pintype "tri_state"))
    )
    (net (code "104") (name "Net-(SR6A-QE)") (class "Default")
      (node (ref "R46") (pin "1") (pinfunction "1_1") (pintype "passive"))
      (node (ref "SR6") (pin "4") (pinfunction "QE_4") (pintype "tri_state"))
    )
    (net (code "105") (name "Net-(SR6A-QF)") (class "Default")
      (node (ref "R47") (pin "1") (pinfunction "1_1") (pintype "passive"))
      (node (ref "SR6") (pin "5") (pinfunction "QF_5") (pintype "tri_state"))
    )
    (net (code "106") (name "Net-(SR6A-QG)") (class "Default")
      (node (ref "R48") (pin "1") (pinfunction "1_1") (pintype "passive"))
      (node (ref "SR6") (pin "6") (pinfunction "QG_6") (pintype "tri_state"))
    )
    (net (code "107") (name "Net-(SR6A-QH)") (class "Default")
      (node (ref "R49") (pin "1") (pinfunction "1_1") (pintype "passive"))
      (node (ref "SR6") (pin "7") (pinfunction "QH_7") (pintype "tri_state"))
    )
    (net (code "108") (name "unconnected-(SR6A-QH*-Pad9)") (class "Default")
      (node (ref "SR6") (pin "9") (pinfunction "QH*_9") (pintype "tri_state"))
    )
  )
)
